# Alimentation.net
KiCad netlist of a schematic drawn in Altium Designer
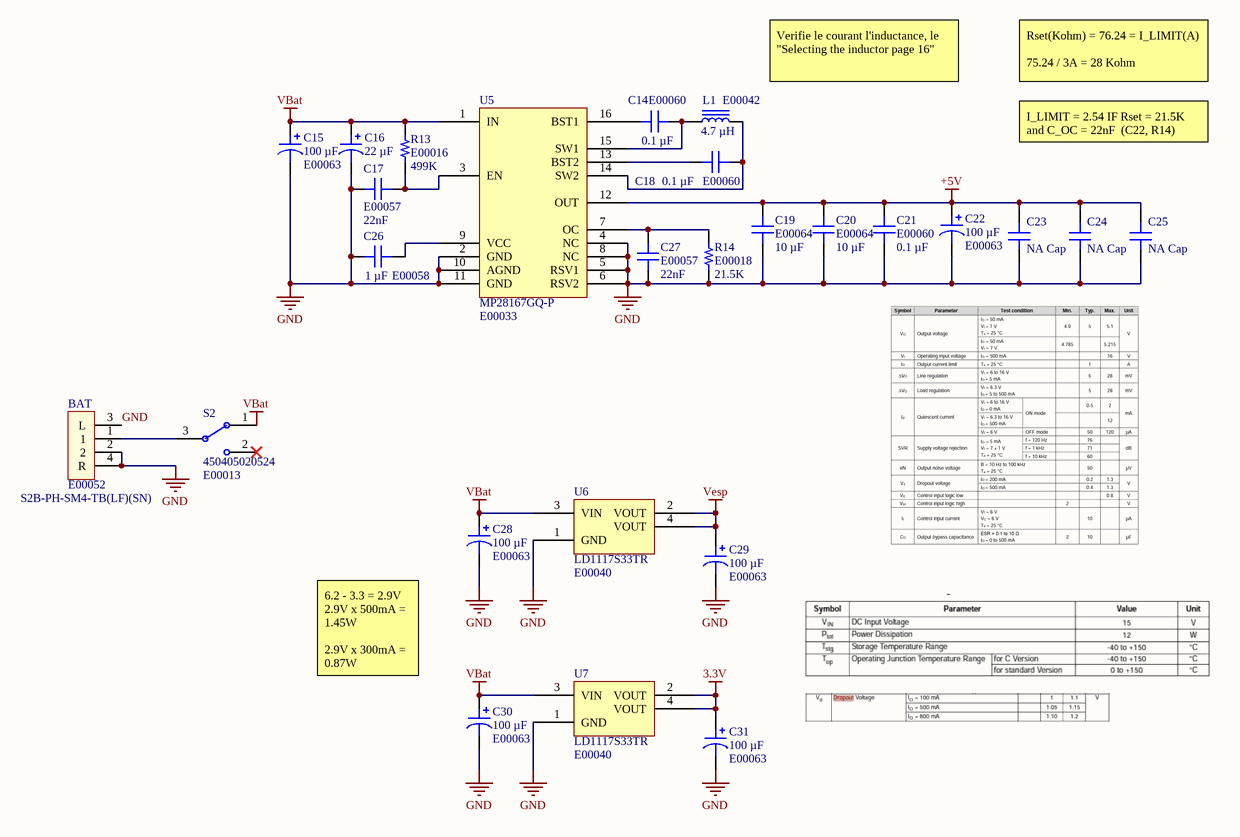
[diagram p0: Alimentation.SchDoc]

(export (version "E")
  (design (tool "Eeschema 10.0.6"))
  (components
    (comp (ref "BAT")
      (value "CONN JST 2P SM 90DEG")
      (footprint "S2B-PH-SM4-TB_LF__SN")
      (description "CONN SM JST 2P")
      (fields
        (field (name "ADAM INVENTORY NUMBER 1") "E00052")
        (field (name "SUPPLIER PART NUMBER 1") "S2B-PH-SM4-TB(LF)(SN)")
        (field (name "COPYRIGHT") "Copyright (C) 2023 Ultra Librarian. All rights reserved.")
      )
      (libsource (lib "ADAM LIBRARY") (part "CONN JST 2P SM 90DEG"))
    )
    (comp (ref "C14")
      (value "0.1 µF")
      (footprint "CAP 0603")
      (description "CAP CER 0.1UF 50V X7R 0603")
      (fields
        (field (name "MANUFACTURER") "KEMET")
        (field (name "TOLERANCE") "±10%")
        (field (name "ADAM INVENTORY NUMBER 1") "E00060")
      )
      (libsource (lib "ADAM LIBRARY") (part "CAP CER 0.1UF 50V X7R 0603"))
    )
    (comp (ref "C15")
      (value "100 µF")
      (footprint "CAP ALSMD ELEC 8.3MM H10.5MM")
      (description "CAP ALUM 100UF 20% 50V SMD")
      (fields
        (field (name "MANUFACTURER") "Nichicon")
        (field (name "TOLERANCE") "±20%")
        (field (name "ADAM INVENTORY NUMBER 1") "E00063")
      )
      (libsource (lib "ADAM LIBRARY") (part "CAP ALUM 100UF 20% 50V SMD"))
    )
    (comp (ref "C16")
      (value "22 µF")
      (footprint "CAP ALSMD 4.3MM H5.4MM")
      (description "CAP ALUM 22UF 20% 16V SMD")
      (fields
        (field (name "PART NUMBER") "EEE-1CA220WAR")
        (field (name "MANUFACTURER") "Panasonic Electronic Components")
      )
      (libsource (lib "Celestial Altium Library - altium_library") (part "Polarised Capacitor"))
    )
    (comp (ref "C17")
      (value "22nF")
      (footprint "CAP 0603")
      (description "CAP CER 22pF 15V 10% 0603, X7R")
      (fields
        (field (name "MANUFACTURER") "Taiyo Yuden")
        (field (name "TOLERANCE") "±10%")
        (field (name "ADAM INVENTORY NUMBER 1") "E00057")
      )
      (libsource (lib "ADAM LIBRARY") (part "CAP CER 22NF 15V 10% 0603"))
    )
    (comp (ref "C18")
      (value "0.1 µF")
      (footprint "CAP 0603")
      (description "CAP CER 0.1UF 50V X7R 0603")
      (fields
        (field (name "MANUFACTURER") "KEMET")
        (field (name "TOLERANCE") "±10%")
        (field (name "ADAM INVENTORY NUMBER 1") "E00060")
      )
      (libsource (lib "ADAM LIBRARY") (part "CAP CER 0.1UF 50V X7R 0603"))
    )
    (comp (ref "C19")
      (value "10 µF")
      (footprint "CAP 0603")
      (description "CAP CER 10UF 6.3V X5R 0603")
      (fields
        (field (name "MANUFACTURER") "Murata Electronics")
        (field (name "TOLERANCE") "±20%")
        (field (name "ADAM INVENTORY NUMBER 1") "E00064")
      )
      (libsource (lib "ADAM LIBRARY") (part "CAP 10UF 6.3V"))
    )
    (comp (ref "C20")
      (value "10 µF")
      (footprint "CAP 0603")
      (description "CAP CER 10UF 6.3V X5R 0603")
      (fields
        (field (name "MANUFACTURER") "Murata Electronics")
        (field (name "TOLERANCE") "±20%")
        (field (name "ADAM INVENTORY NUMBER 1") "E00064")
      )
      (libsource (lib "ADAM LIBRARY") (part "CAP 10UF 6.3V"))
    )
    (comp (ref "C21")
      (value "0.1 µF")
      (footprint "CAP 0603")
      (description "CAP CER 0.1UF 50V X7R 0603")
      (fields
        (field (name "MANUFACTURER") "KEMET")
        (field (name "TOLERANCE") "±10%")
        (field (name "ADAM INVENTORY NUMBER 1") "E00060")
      )
      (libsource (lib "ADAM LIBRARY") (part "CAP CER 0.1UF 50V X7R 0603"))
    )
    (comp (ref "C22")
      (value "100 µF")
      (footprint "CAP ALSMD ELEC 8.3MM H10.5MM")
      (description "CAP ALUM 100UF 20% 50V SMD")
      (fields
        (field (name "MANUFACTURER") "Nichicon")
        (field (name "TOLERANCE") "±20%")
        (field (name "ADAM INVENTORY NUMBER 1") "E00063")
      )
      (libsource (lib "ADAM LIBRARY") (part "CAP ALUM 100UF 20% 50V SMD"))
    )
    (comp (ref "C23")
      (value "NA Cap")
      (footprint "CAP 0603")
      (description "No capacitor, just in case")
      (libsource (lib "ADAM LIBRARY") (part "NA Cap 0603"))
    )
    (comp (ref "C24")
      (value "NA Cap")
      (footprint "CAP 0603")
      (description "No capacitor, just in case")
      (libsource (lib "ADAM LIBRARY") (part "NA Cap 0603"))
    )
    (comp (ref "C25")
      (value "NA Cap")
      (footprint "CAP 0603")
      (description "No capacitor, just in case")
      (libsource (lib "ADAM LIBRARY") (part "NA Cap 0603"))
    )
    (comp (ref "C26")
      (value "1 µF")
      (footprint "CAP 0603")
      (description "CAP CER 1UF 16V X7R 0603")
      (fields
        (field (name "MANUFACTURER") "KEMET")
        (field (name "TOLERANCE") "±10%")
        (field (name "ADAM INVENTORY NUMBER 1") "E00058")
      )
      (libsource (lib "ADAM LIBRARY") (part "CAP CER 1UF 16V X7R 0603"))
    )
    (comp (ref "C27")
      (value "22nF")
      (footprint "CAP 0603")
      (description "CAP CER 22pF 15V 10% 0603, X7R")
      (fields
        (field (name "MANUFACTURER") "Taiyo Yuden")
        (field (name "TOLERANCE") "±10%")
        (field (name "ADAM INVENTORY NUMBER 1") "E00057")
      )
      (libsource (lib "ADAM LIBRARY") (part "CAP CER 22NF 15V 10% 0603"))
    )
    (comp (ref "C28")
      (value "100 µF")
      (footprint "CAP ALSMD ELEC 8.3MM H10.5MM")
      (description "CAP ALUM 100UF 20% 50V SMD")
      (fields
        (field (name "MANUFACTURER") "Nichicon")
        (field (name "TOLERANCE") "±20%")
        (field (name "ADAM INVENTORY NUMBER 1") "E00063")
      )
      (libsource (lib "ADAM LIBRARY") (part "CAP ALUM 100UF 20% 50V SMD"))
    )
    (comp (ref "C29")
      (value "100 µF")
      (footprint "CAP ALSMD ELEC 8.3MM H10.5MM")
      (description "CAP ALUM 100UF 20% 50V SMD")
      (fields
        (field (name "MANUFACTURER") "Nichicon")
        (field (name "TOLERANCE") "±20%")
        (field (name "ADAM INVENTORY NUMBER 1") "E00063")
      )
      (libsource (lib "ADAM LIBRARY") (part "CAP ALUM 100UF 20% 50V SMD"))
    )
    (comp (ref "C30")
      (value "100 µF")
      (footprint "CAP ALSMD ELEC 8.3MM H10.5MM")
      (description "CAP ALUM 100UF 20% 50V SMD")
      (fields
        (field (name "MANUFACTURER") "Nichicon")
        (field (name "TOLERANCE") "±20%")
        (field (name "ADAM INVENTORY NUMBER 1") "E00063")
      )
      (libsource (lib "ADAM LIBRARY") (part "CAP ALUM 100UF 20% 50V SMD"))
    )
    (comp (ref "C31")
      (value "100 µF")
      (footprint "CAP ALSMD ELEC 8.3MM H10.5MM")
      (description "CAP ALUM 100UF 20% 50V SMD")
      (fields
        (field (name "MANUFACTURER") "Nichicon")
        (field (name "TOLERANCE") "±20%")
        (field (name "ADAM INVENTORY NUMBER 1") "E00063")
      )
      (libsource (lib "ADAM LIBRARY") (part "CAP ALUM 100UF 20% 50V SMD"))
    )
    (comp (ref "L1")
      (value "4.7 µH")
      (footprint "IND 4.7UH 4.6A")
      (description "FIXED IND 4.7UH 4.6A 53 MOHM SMD")
      (fields
        (field (name "MANUFACTURER") "Bourns Inc.")
        (field (name "TOLERANCE") "±20%")
        (field (name "ADAM INVENTORY NUMBER 1") "E00042")
      )
      (libsource (lib "ADAM LIBRARY") (part "IND 4.7UH 4.6A"))
    )
    (comp (ref "R13")
      (value "499K")
      (footprint "RES 0603")
      (description "RES SMD 499K OHM 1% 1/4W 0603")
      (fields
        (field (name "MANUFACTURER") "Vishay Dale")
        (field (name "TOLERANCE") "±1%")
        (field (name "ADAM INVENTORY NUMBER 1") "E00016")
      )
      (libsource (lib "ADAM LIBRARY") (part "RES SMD 499K OHM"))
    )
    (comp (ref "R14")
      (value "21.5K")
      (footprint "RES 0603")
      (description "RES SMD 21.5K OHM 0.1% 1/5W 0603")
      (fields
        (field (name "MANUFACTURER") "Panasonic Electronic Components")
        (field (name "TOLERANCE") "±0.1%")
        (field (name "ADAM INVENTORY NUMBER 1") "E00018")
      )
      (libsource (lib "ADAM LIBRARY") (part "RES SMD 21.5K OHM"))
    )
    (comp (ref "S2")
      (value "450405020524")
      (footprint "SL 3Pos Switch")
      (description "SMT 8.7 X 3.0 MM MINI SLIDE SWIT")
      (fields
        (field (name "MANUFACTURER") "Würth Elektronik")
        (field (name "ADAM INVENTORY NUMBER 1") "E00013")
        (field (name "PUBLISHER") "Wurth Elektronik")
      )
      (libsource (lib "ADAM LIBRARY") (part "SLIDE SWIT"))
    )
    (comp (ref "U5")
      (value "MP28167GQ-P")
      (footprint "MP2816GQ-P")
      (description "Buck-Boost Switching Regulator IC Positive Fixed 5V 1 Output 3A 16-PowerVFQFN")
      (fields (field (name "ADAM INVENTORY NUMBER 1") "E00033"))
      (libsource (lib "ADAM LIBRARY") (part "MP28167GQ-P"))
    )
    (comp (ref "U6")
      (value "LD1117S33TR")
      (footprint "SOT-223")
      (description "IC REG LINEAR 3.3V 800MA SOT223")
      (fields
        (field (name "MANUFACTURER") "STMicroelectronics")
        (field (name "ADAM INVENTORY NUMBER 1") "E00040")
      )
      (libsource (lib "ADAM LIBRARY") (part "LD1117S33TR"))
    )
    (comp (ref "U7")
      (value "LD1117S33TR")
      (footprint "SOT-223")
      (description "IC REG LINEAR 3.3V 800MA SOT223")
      (fields
        (field (name "MANUFACTURER") "STMicroelectronics")
        (field (name "ADAM INVENTORY NUMBER 1") "E00040")
      )
      (libsource (lib "ADAM LIBRARY") (part "LD1117S33TR"))
    )
  )
  (nets
    (net (code "1") (name "+5V") (class "Default")
      (node (ref "C19") (pin "2") (pinfunction "2_2") (pintype "passive"))
      (node (ref "C20") (pin "2") (pinfunction "2_2") (pintype "passive"))
      (node (ref "C21") (pin "2") (pinfunction "2_2") (pintype "passive"))
      (node (ref "C22") (pin "1") (pinfunction "1_1") (pintype "passive"))
      (node (ref "C23") (pin "1") (pinfunction "1_1") (pintype "passive"))
      (node (ref "C24") (pin "1") (pinfunction "1_1") (pintype "passive"))
      (node (ref "C25") (pin "1") (pinfunction "1_1") (pintype "passive"))
      (node (ref "U5") (pin "12") (pinfunction "OUT_12") (pintype "passive"))
    )
    (net (code "2") (name "3.3V") (class "Default")
      (node (ref "C31") (pin "1") (pinfunction "1_1") (pintype "passive"))
      (node (ref "U7") (pin "2") (pinfunction "VOUT_2") (pintype "passive"))
      (node (ref "U7") (pin "4") (pinfunction "VOUT_4") (pintype "passive"))
    )
    (net (code "3") (name "GND") (class "Default")
      (node (ref "BAT") (pin "2") (pinfunction "2_2") (pintype "passive"))
      (node (ref "BAT") (pin "3") (pinfunction "L_3") (pintype "passive"))
      (node (ref "BAT") (pin "4") (pinfunction "R_4") (pintype "passive"))
      (node (ref "C15") (pin "2") (pinfunction "2_2") (pintype "passive"))
      (node (ref "C16") (pin "2") (pinfunction "2_2") (pintype "passive"))
      (node (ref "C17") (pin "1") (pinfunction "1_1") (pintype "passive"))
      (node (ref "C19") (pin "1") (pinfunction "1_1") (pintype "passive"))
      (node (ref "C20") (pin "1") (pinfunction "1_1") (pintype "passive"))
      (node (ref "C21") (pin "1") (pinfunction "1_1") (pintype "passive"))
      (node (ref "C22") (pin "2") (pinfunction "2_2") (pintype "passive"))
      (node (ref "C23") (pin "2") (pinfunction "2_2") (pintype "passive"))
      (node (ref "C24") (pin "2") (pinfunction "2_2") (pintype "passive"))
      (node (ref "C25") (pin "2") (pinfunction "2_2") (pintype "passive"))
      (node (ref "C26") (pin "2") (pinfunction "2_2") (pintype "passive"))
      (node (ref "C27") (pin "1") (pinfunction "1_1") (pintype "passive"))
      (node (ref "C28") (pin "2") (pinfunction "2_2") (pintype "passive"))
      (node (ref "C29") (pin "2") (pinfunction "2_2") (pintype "passive"))
      (node (ref "C30") (pin "2") (pinfunction "2_2") (pintype "passive"))
      (node (ref "C31") (pin "2") (pinfunction "2_2") (pintype "passive"))
      (node (ref "R14") (pin "1") (pinfunction "1_1") (pintype "passive"))
      (node (ref "U5") (pin "10") (pinfunction "AGND_10") (pintype "passive"))
      (node (ref "U5") (pin "11") (pinfunction "GND_11") (pintype "passive"))
      (node (ref "U5") (pin "2") (pinfunction "GND_2") (pintype "passive"))
      (node (ref "U5") (pin "4") (pinfunction "NC_4") (pintype "passive"))
      (node (ref "U5") (pin "5") (pinfunction "RSV1_5") (pintype "passive"))
      (node (ref "U5") (pin "6") (pinfunction "RSV2_6") (pintype "passive"))
      (node (ref "U5") (pin "8") (pinfunction "NC_8") (pintype "passive"))
      (node (ref "U6") (pin "1") (pinfunction "GND_1") (pintype "passive"))
      (node (ref "U7") (pin "1") (pinfunction "GND_1") (pintype "passive"))
    )
    (net (code "4") (name "Net-(S2-COM)") (class "Default")
      (node (ref "BAT") (pin "1") (pinfunction "1_1") (pintype "passive"))
      (node (ref "S2") (pin "3") (pinfunction "COM_3") (pintype "passive"))
    )
    (net (code "5") (name "Net-(U5-BST1)") (class "Default")
      (node (ref "C14") (pin "2") (pinfunction "2_2") (pintype "passive"))
      (node (ref "U5") (pin "16") (pinfunction "BST1_16") (pintype "passive"))
    )
    (net (code "6") (name "Net-(U5-BST2)") (class "Default")
      (node (ref "C18") (pin "2") (pinfunction "2_2") (pintype "passive"))
      (node (ref "U5") (pin "13") (pinfunction "BST2_13") (pintype "passive"))
    )
    (net (code "7") (name "Net-(U5-EN)") (class "Default")
      (node (ref "C17") (pin "2") (pinfunction "2_2") (pintype "passive"))
      (node (ref "R13") (pin "1") (pinfunction "1_1") (pintype "passive"))
      (node (ref "U5") (pin "3") (pinfunction "EN_3") (pintype "passive"))
    )
    (net (code "8") (name "Net-(U5-OC)") (class "Default")
      (node (ref "C27") (pin "2") (pinfunction "2_2") (pintype "passive"))
      (node (ref "R14") (pin "2") (pinfunction "2_2") (pintype "passive"))
      (node (ref "U5") (pin "7") (pinfunction "OC_7") (pintype "passive"))
    )
    (net (code "9") (name "Net-(U5-SW1)") (class "Default")
      (node (ref "C14") (pin "1") (pinfunction "1_1") (pintype "passive"))
      (node (ref "L1") (pin "1") (pinfunction "1_1") (pintype "passive"))
      (node (ref "U5") (pin "15") (pinfunction "SW1_15") (pintype "passive"))
    )
    (net (code "10") (name "Net-(U5-SW2)") (class "Default")
      (node (ref "C18") (pin "1") (pinfunction "1_1") (pintype "passive"))
      (node (ref "L1") (pin "2") (pinfunction "2_2") (pintype "passive"))
      (node (ref "U5") (pin "14") (pinfunction "SW2_14") (pintype "passive"))
    )
    (net (code "11") (name "Net-(U5-VCC)") (class "Default")
      (node (ref "C26") (pin "1") (pinfunction "1_1") (pintype "passive"))
      (node (ref "U5") (pin "9") (pinfunction "VCC_9") (pintype "passive"))
    )
    (net (code "12") (name "VBat") (class "Default")
      (node (ref "C15") (pin "1") (pinfunction "1_1") (pintype "passive"))
      (node (ref "C16") (pin "1") (pinfunction "1_1") (pintype "passive"))
      (node (ref "C28") (pin "1") (pinfunction "1_1") (pintype "passive"))
      (node (ref "C30") (pin "1") (pinfunction "1_1") (pintype "passive"))
      (node (ref "R13") (pin "2") (pinfunction "2_2") (pintype "passive"))
      (node (ref "S2") (pin "1") (pinfunction "1_1") (pintype "passive"))
      (node (ref "U5") (pin "1") (pinfunction "IN_1") (pintype "passive"))
      (node (ref "U6") (pin "3") (pinfunction "VIN_3") (pintype "passive"))
      (node (ref "U7") (pin "3") (pinfunction "VIN_3") (pintype "passive"))
    )
    (net (code "13") (name "Vesp") (class "Default")
      (node (ref "C29") (pin "1") (pinfunction "1_1") (pintype "passive"))
      (node (ref "U6") (pin "2") (pinfunction "VOUT_2") (pintype "passive"))
      (node (ref "U6") (pin "4") (pinfunction "VOUT_4") (pintype "passive"))
    )
    (net (code "14") (name "unconnected-(S2-Pad2)") (class "Default")
      (node (ref "S2") (pin "2") (pinfunction "2_2") (pintype "passive+no_connect"))
    )
  )
)
